# PSU.net
KiCad netlist of a schematic drawn in Altium Designer
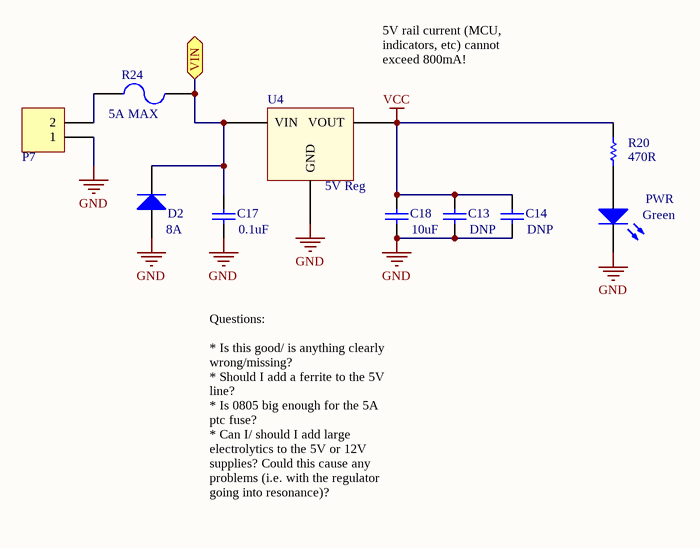
[diagram p0: PSU.SchDoc]

(export (version "E")
  (design (tool "Eeschema 10.0.6"))
  (components
    (comp (ref "C13")
      (value "DNP")
      (footprint "0805")
      (description "Capacitor")
      (fields (field (name "Comment") "Cap") (field (name "PUBLISHER") "Altium Limited"))
      (libsource (lib "Miscellaneous Devices") (part "Cap"))
    )
    (comp (ref "C14")
      (value "DNP")
      (footprint "0805")
      (description "Capacitor")
      (fields (field (name "Comment") "Cap") (field (name "PUBLISHER") "Altium Limited"))
      (libsource (lib "Miscellaneous Devices") (part "Cap"))
    )
    (comp (ref "C17")
      (value "0.1uF")
      (footprint "0805")
      (description "Capacitor")
      (fields (field (name "Comment") "Cap") (field (name "PUBLISHER") "Altium Limited"))
      (libsource (lib "Miscellaneous Devices") (part "Cap"))
    )
    (comp (ref "C18")
      (value "10uF")
      (footprint "0805")
      (description "Capacitor")
      (fields (field (name "Comment") "Cap") (field (name "PUBLISHER") "Altium Limited"))
      (libsource (lib "Miscellaneous Devices") (part "Cap"))
    )
    (comp (ref "D2")
      (value "Diode S8MC")
      (footprint "S8MC Diode")
      (description "Standard Diode")
      (fields
        (field (name "DIGI-KEY PART NO.") "S8MCDICT-ND")
        (field (name "MANUFACTURER PART NO.") "S8MC-13")
        (field (name "MAX CURRENT") "8A")
      )
      (libsource (lib "Semiconductors") (part "Diode S8MC"))
    )
    (comp (ref "P7")
      (value "Screw Terminal")
      (footprint "Screw Terminal")
      (fields
        (field (name "DIGI-KEY PART NO.") "277-1667-ND")
        (field (name "MANUFACTURER PART NO.") "1935161")
      )
      (libsource (lib "Connectors") (part "Screw Terminal"))
    )
    (comp (ref "PWR")
      (value "LED0")
      (footprint "0805")
      (description "Typical INFRARED GaAs LED")
      (fields (field (name "COLOR") "Green") (field (name "PUBLISHER") "Altium Limited"))
      (libsource (lib "Miscellaneous Devices") (part "LED0"))
    )
    (comp (ref "R20")
      (value "470R")
      (footprint "6-0805_N")
      (description "Resistor")
      (fields (field (name "Comment") "Res1") (field (name "PUBLISHER") "Altium Limited"))
      (libsource (lib "Miscellaneous Devices") (part "Res1"))
    )
    (comp (ref "R24")
      (value "Chip PTC")
      (footprint "0805")
      (description "PTC")
      (fields (field (name "ITRIP") "5A MAX"))
      (libsource (lib "Circuit Protection") (part "PTC"))
    )
    (comp (ref "U4")
      (value "5V Reg")
      (footprint "4-Pin SOT223")
      (description "5V Linear Regulator")
      (fields
        (field (name "DIGI-KEY PART NO.") "497-1243-1-ND")
        (field (name "MANUFACTURER PART NO.") "LD1117S50CTR")
      )
      (libsource (lib "Power ICs") (part "5V Linear Regulator"))
    )
  )
  (nets
    (net (code "1") (name "/VIN") (class "Default")
      (node (ref "C17") (pin "2") (pinfunction "2_2") (pintype "passive"))
      (node (ref "D2") (pin "2") (pinfunction "C_2") (pintype "passive"))
      (node (ref "R24") (pin "2") (pinfunction "2_2") (pintype "passive"))
      (node (ref "U4") (pin "3") (pinfunction "VIN_3") (pintype "passive"))
    )
    (net (code "2") (name "GND") (class "Default")
      (node (ref "C13") (pin "1") (pinfunction "1_1") (pintype "passive"))
      (node (ref "C14") (pin "1") (pinfunction "1_1") (pintype "passive"))
      (node (ref "C17") (pin "1") (pinfunction "1_1") (pintype "passive"))
      (node (ref "C18") (pin "1") (pinfunction "1_1") (pintype "passive"))
      (node (ref "D2") (pin "1") (pinfunction "A_1") (pintype "passive"))
      (node (ref "P7") (pin "1") (pinfunction "1_1") (pintype "passive"))
      (node (ref "PWR") (pin "2") (pinfunction "K_2") (pintype "passive"))
      (node (ref "U4") (pin "1") (pinfunction "GND_1") (pintype "passive"))
    )
    (net (code "3") (name "Net-(P7-Pad2)") (class "Default")
      (node (ref "P7") (pin "2") (pinfunction "2_2") (pintype "passive"))
      (node (ref "R24") (pin "1") (pinfunction "1_1") (pintype "passive"))
    )
    (net (code "4") (name "Net-(PWR-A)") (class "Default")
      (node (ref "PWR") (pin "1") (pinfunction "A_1") (pintype "passive"))
      (node (ref "R20") (pin "1") (pinfunction "1_1") (pintype "passive"))
    )
    (net (code "5") (name "VCC") (class "Default")
      (node (ref "C13") (pin "2") (pinfunction "2_2") (pintype "passive"))
      (node (ref "C14") (pin "2") (pinfunction "2_2") (pintype "passive"))
      (node (ref "C18") (pin "2") (pinfunction "2_2") (pintype "passive"))
      (node (ref "R20") (pin "2") (pinfunction "2_2") (pintype "passive"))
      (node (ref "U4") (pin "2") (pinfunction "VOUT_2") (pintype "passive"))
    )
  )
)
